# zf1.net
KiCad netlist of a schematic drawn in EAGLE
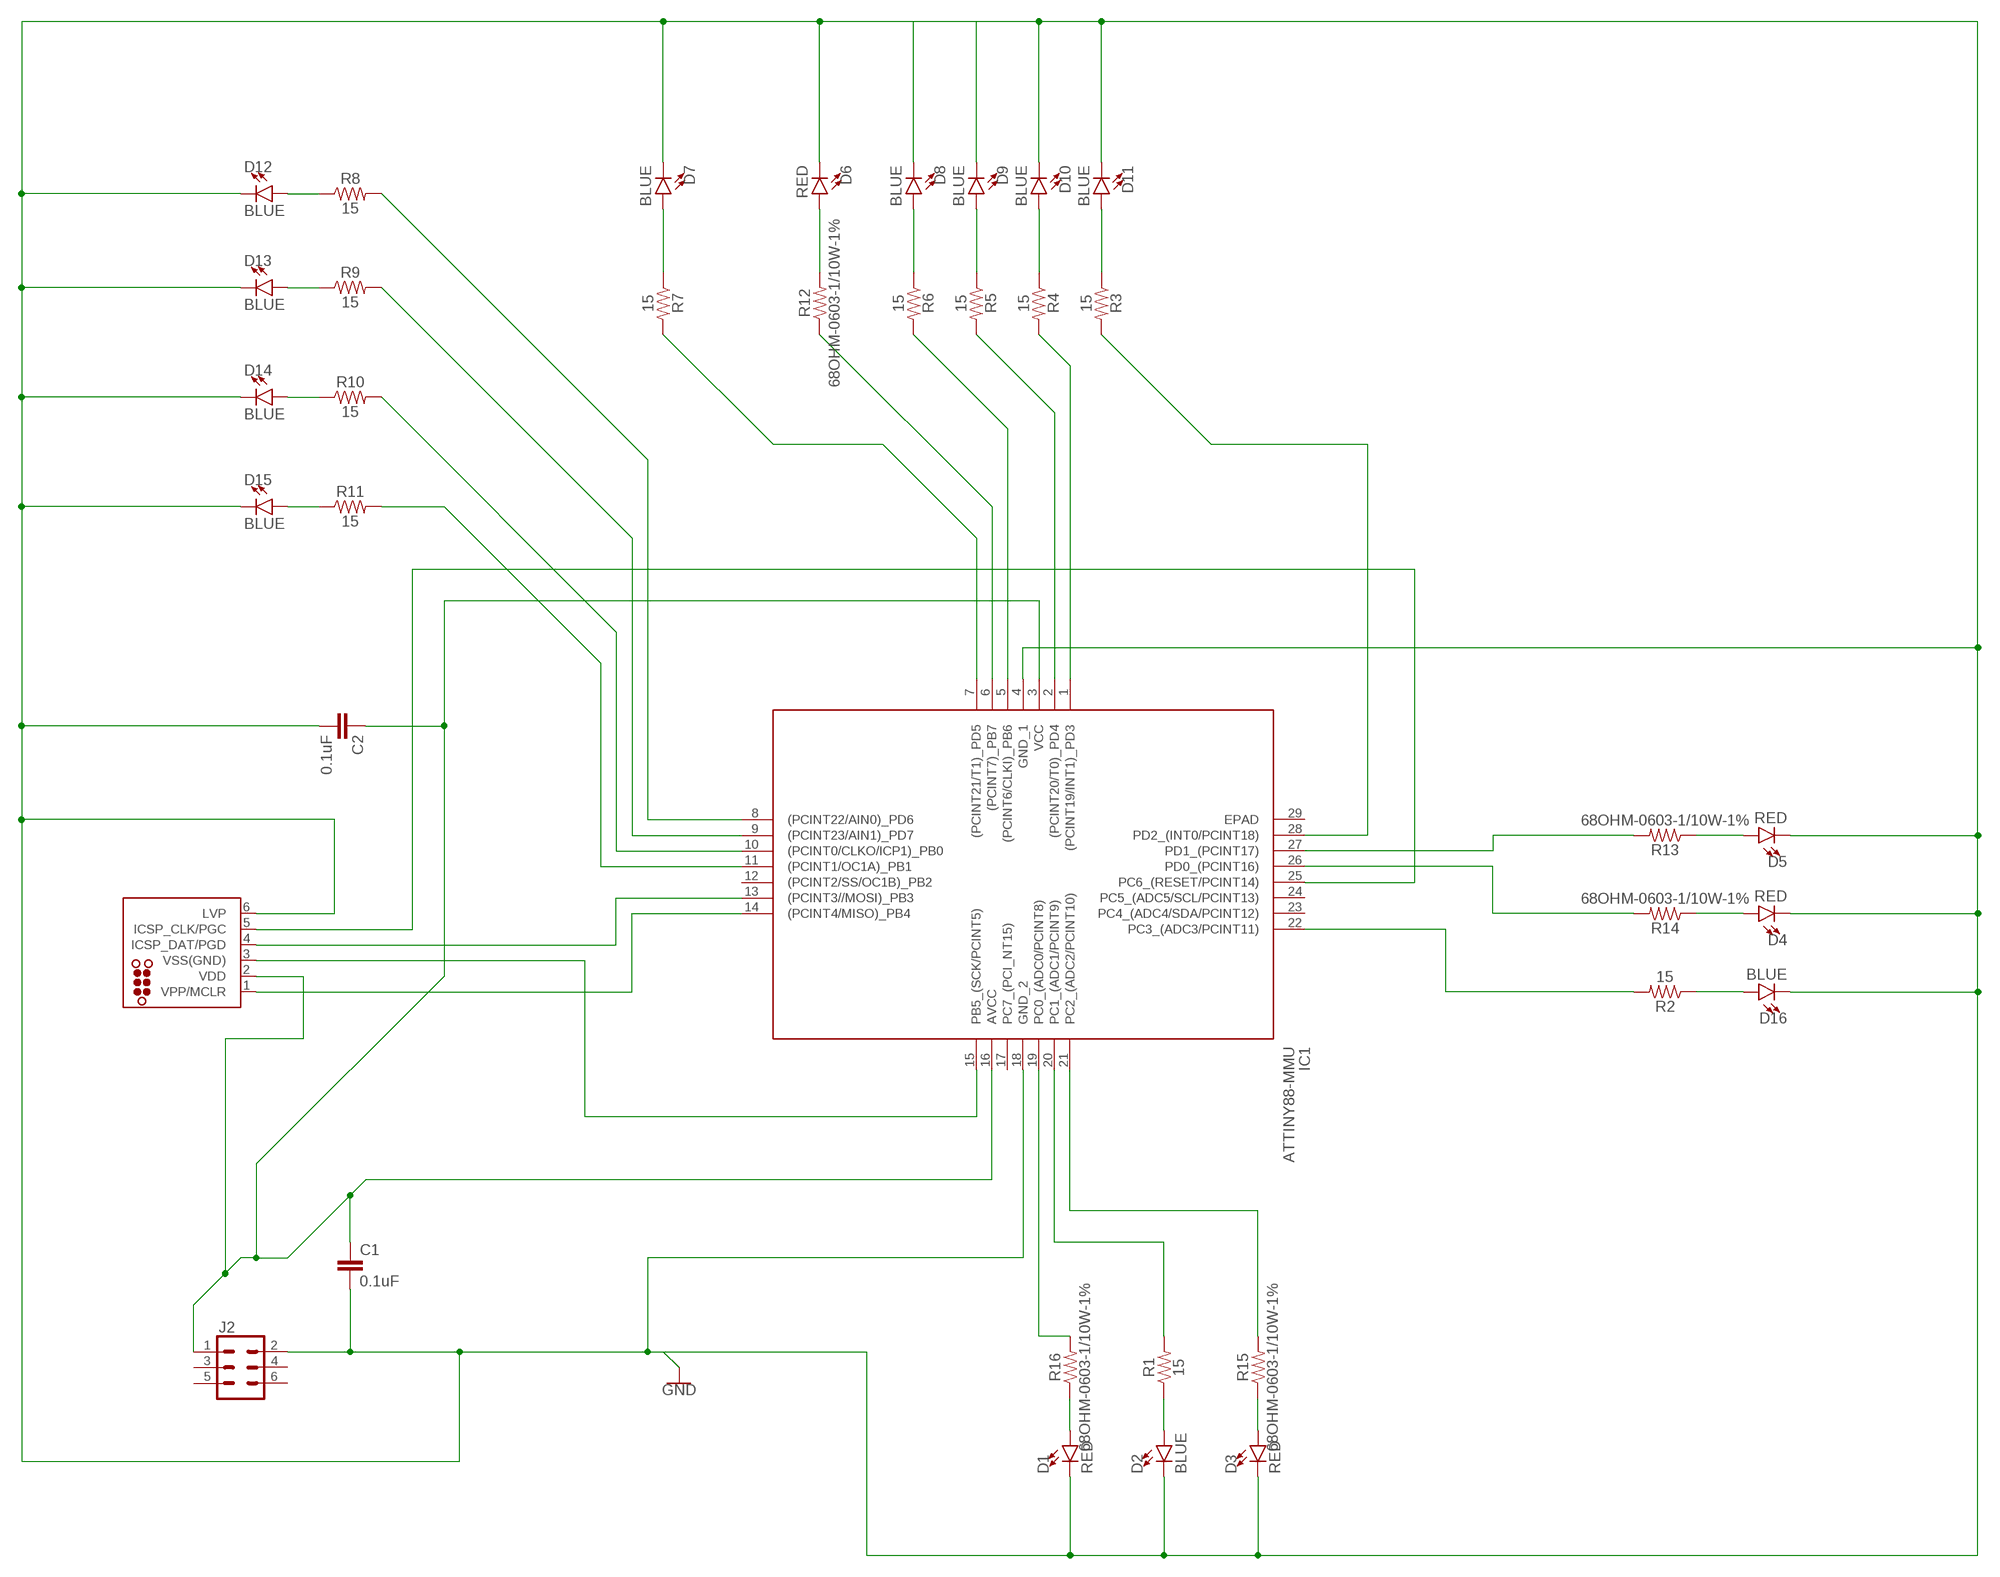
[diagram p0: schematic, sheet 1]

(export (version "E")
  (design (tool "Eeschema 10.0.6"))
  (components
    (comp (ref "C1")
      (value "0.1uF")
      (footprint "eagle-import:0603")
      (libsource (lib "eagle-import") (part "0.1UF-0603-25V-(+80/-20%)"))
    )
    (comp (ref "C2")
      (value "0.1uF")
      (footprint "eagle-import:0603")
      (libsource (lib "eagle-import") (part "0.1UF-0603-25V-(+80/-20%)"))
    )
    (comp (ref "D1")
      (value "RED")
      (footprint "eagle-import:LED-0603")
      (libsource (lib "eagle-import") (part "LED-RED0603"))
    )
    (comp (ref "D2")
      (value "BLUE")
      (footprint "eagle-import:LED-0603")
      (libsource (lib "eagle-import") (part "LED-BLUE0603"))
    )
    (comp (ref "D3")
      (value "RED")
      (footprint "eagle-import:LED-0603")
      (libsource (lib "eagle-import") (part "LED-RED0603"))
    )
    (comp (ref "D4")
      (value "RED")
      (footprint "eagle-import:LED-0603")
      (libsource (lib "eagle-import") (part "LED-RED0603"))
    )
    (comp (ref "D5")
      (value "RED")
      (footprint "eagle-import:LED-0603")
      (libsource (lib "eagle-import") (part "LED-RED0603"))
    )
    (comp (ref "D6")
      (value "RED")
      (footprint "eagle-import:LED-0603")
      (libsource (lib "eagle-import") (part "LED-RED0603"))
    )
    (comp (ref "D7")
      (value "BLUE")
      (footprint "eagle-import:LED-0603")
      (libsource (lib "eagle-import") (part "LED-BLUE0603"))
    )
    (comp (ref "D8")
      (value "BLUE")
      (footprint "eagle-import:LED-0603")
      (libsource (lib "eagle-import") (part "LED-BLUE0603"))
    )
    (comp (ref "D9")
      (value "BLUE")
      (footprint "eagle-import:LED-0603")
      (libsource (lib "eagle-import") (part "LED-BLUE0603"))
    )
    (comp (ref "D10")
      (value "BLUE")
      (footprint "eagle-import:LED-0603")
      (libsource (lib "eagle-import") (part "LED-BLUE0603"))
    )
    (comp (ref "D11")
      (value "BLUE")
      (footprint "eagle-import:LED-0603")
      (libsource (lib "eagle-import") (part "LED-BLUE0603"))
    )
    (comp (ref "D12")
      (value "BLUE")
      (footprint "eagle-import:LED-0603")
      (libsource (lib "eagle-import") (part "LED-BLUE0603"))
    )
    (comp (ref "D13")
      (value "BLUE")
      (footprint "eagle-import:LED-0603")
      (libsource (lib "eagle-import") (part "LED-BLUE0603"))
    )
    (comp (ref "D14")
      (value "BLUE")
      (footprint "eagle-import:LED-0603")
      (libsource (lib "eagle-import") (part "LED-BLUE0603"))
    )
    (comp (ref "D15")
      (value "BLUE")
      (footprint "eagle-import:LED-0603")
      (libsource (lib "eagle-import") (part "LED-BLUE0603"))
    )
    (comp (ref "D16")
      (value "BLUE")
      (footprint "eagle-import:LED-0603")
      (libsource (lib "eagle-import") (part "LED-BLUE0603"))
    )
    (comp (ref "IC1")
      (value "ATTINY88-MMU")
      (footprint "eagle-import:QFN45P400X400X100-29N")
      (fields (field (name "MOUSER_PART_NUMBER") "556-ATTINY88-MMU"))
      (libsource (lib "eagle-import") (part "ATTINY88-MMU"))
    )
    (comp (ref "J1")
      (value "TC2030-MCP-NL")
      (footprint "eagle-import:TC2030-MCP-NL")
      (libsource (lib "eagle-import") (part "TC2030-MCP-NL"))
    )
    (comp (ref "J2")
      (value "CONN_03X2SHROUD")
      (footprint "eagle-import:2X3-SHROUDED")
      (libsource (lib "eagle-import") (part "CONN_03X2SHROUD"))
    )
    (comp (ref "R1")
      (value "15")
      (footprint "eagle-import:0603")
      (libsource (lib "eagle-import") (part "15OHM-0603-1/10W-1%"))
    )
    (comp (ref "R2")
      (value "15")
      (footprint "eagle-import:0603")
      (libsource (lib "eagle-import") (part "15OHM-0603-1/10W-1%"))
    )
    (comp (ref "R3")
      (value "15")
      (footprint "eagle-import:0603")
      (libsource (lib "eagle-import") (part "15OHM-0603-1/10W-1%"))
    )
    (comp (ref "R4")
      (value "15")
      (footprint "eagle-import:0603")
      (libsource (lib "eagle-import") (part "15OHM-0603-1/10W-1%"))
    )
    (comp (ref "R5")
      (value "15")
      (footprint "eagle-import:0603")
      (libsource (lib "eagle-import") (part "15OHM-0603-1/10W-1%"))
    )
    (comp (ref "R6")
      (value "15")
      (footprint "eagle-import:0603")
      (libsource (lib "eagle-import") (part "15OHM-0603-1/10W-1%"))
    )
    (comp (ref "R7")
      (value "15")
      (footprint "eagle-import:0603")
      (libsource (lib "eagle-import") (part "15OHM-0603-1/10W-1%"))
    )
    (comp (ref "R8")
      (value "15")
      (footprint "eagle-import:0603")
      (libsource (lib "eagle-import") (part "15OHM-0603-1/10W-1%"))
    )
    (comp (ref "R9")
      (value "15")
      (footprint "eagle-import:0603")
      (libsource (lib "eagle-import") (part "15OHM-0603-1/10W-1%"))
    )
    (comp (ref "R10")
      (value "15")
      (footprint "eagle-import:0603")
      (libsource (lib "eagle-import") (part "15OHM-0603-1/10W-1%"))
    )
    (comp (ref "R11")
      (value "15")
      (footprint "eagle-import:0603")
      (libsource (lib "eagle-import") (part "15OHM-0603-1/10W-1%"))
    )
    (comp (ref "R12")
      (value "68OHM-0603-1/10W-1%")
      (footprint "eagle-import:0603")
      (libsource (lib "eagle-import") (part "68OHM-0603-1/10W-1%"))
    )
    (comp (ref "R13")
      (value "68OHM-0603-1/10W-1%")
      (footprint "eagle-import:0603")
      (libsource (lib "eagle-import") (part "68OHM-0603-1/10W-1%"))
    )
    (comp (ref "R14")
      (value "68OHM-0603-1/10W-1%")
      (footprint "eagle-import:0603")
      (libsource (lib "eagle-import") (part "68OHM-0603-1/10W-1%"))
    )
    (comp (ref "R15")
      (value "68OHM-0603-1/10W-1%")
      (footprint "eagle-import:0603")
      (libsource (lib "eagle-import") (part "68OHM-0603-1/10W-1%"))
    )
    (comp (ref "R16")
      (value "68OHM-0603-1/10W-1%")
      (footprint "eagle-import:0603")
      (libsource (lib "eagle-import") (part "68OHM-0603-1/10W-1%"))
    )
  )
  (nets
    (net (code "1") (name "GND") (class "Default")
      (node (ref "C1") (pin "2") (pinfunction "2_2") (pintype "passive"))
      (node (ref "C2") (pin "2") (pinfunction "2_2") (pintype "passive"))
      (node (ref "D1") (pin "C") (pinfunction "C_C") (pintype "passive"))
      (node (ref "D10") (pin "C") (pinfunction "C_C") (pintype "passive"))
      (node (ref "D11") (pin "C") (pinfunction "C_C") (pintype "passive"))
      (node (ref "D12") (pin "C") (pinfunction "C_C") (pintype "passive"))
      (node (ref "D13") (pin "C") (pinfunction "C_C") (pintype "passive"))
      (node (ref "D14") (pin "C") (pinfunction "C_C") (pintype "passive"))
      (node (ref "D15") (pin "C") (pinfunction "C_C") (pintype "passive"))
      (node (ref "D16") (pin "C") (pinfunction "C_C") (pintype "passive"))
      (node (ref "D2") (pin "C") (pinfunction "C_C") (pintype "passive"))
      (node (ref "D3") (pin "C") (pinfunction "C_C") (pintype "passive"))
      (node (ref "D4") (pin "C") (pinfunction "C_C") (pintype "passive"))
      (node (ref "D5") (pin "C") (pinfunction "C_C") (pintype "passive"))
      (node (ref "D6") (pin "C") (pinfunction "C_C") (pintype "passive"))
      (node (ref "D7") (pin "C") (pinfunction "C_C") (pintype "passive"))
      (node (ref "D8") (pin "C") (pinfunction "C_C") (pintype "passive"))
      (node (ref "D9") (pin "C") (pinfunction "C_C") (pintype "passive"))
      (node (ref "IC1") (pin "18") (pinfunction "GND_2_18") (pintype "bidirectional"))
      (node (ref "IC1") (pin "4") (pinfunction "GND_1_4") (pintype "bidirectional"))
      (node (ref "J1") (pin "6") (pinfunction "LVP_6") (pintype "bidirectional"))
      (node (ref "J2") (pin "2") (pinfunction "2_2") (pintype "bidirectional"))
    )
    (net (code "2") (name "Net-(D1-PadA)") (class "Default")
      (node (ref "D1") (pin "A") (pinfunction "A_A") (pintype "passive"))
      (node (ref "R16") (pin "1") (pinfunction "1_1") (pintype "passive"))
    )
    (net (code "3") (name "Net-(D2-PadA)") (class "Default")
      (node (ref "D2") (pin "A") (pinfunction "A_A") (pintype "passive"))
      (node (ref "R1") (pin "1") (pinfunction "1_1") (pintype "passive"))
    )
    (net (code "4") (name "Net-(D3-PadA)") (class "Default")
      (node (ref "D3") (pin "A") (pinfunction "A_A") (pintype "passive"))
      (node (ref "R15") (pin "1") (pinfunction "1_1") (pintype "passive"))
    )
    (net (code "5") (name "Net-(D4-PadA)") (class "Default")
      (node (ref "D4") (pin "A") (pinfunction "A_A") (pintype "passive"))
      (node (ref "R14") (pin "1") (pinfunction "1_1") (pintype "passive"))
    )
    (net (code "6") (name "Net-(D5-PadA)") (class "Default")
      (node (ref "D5") (pin "A") (pinfunction "A_A") (pintype "passive"))
      (node (ref "R13") (pin "1") (pinfunction "1_1") (pintype "passive"))
    )
    (net (code "7") (name "Net-(D6-PadA)") (class "Default")
      (node (ref "D6") (pin "A") (pinfunction "A_A") (pintype "passive"))
      (node (ref "R12") (pin "2") (pinfunction "2_2") (pintype "passive"))
    )
    (net (code "8") (name "Net-(D7-PadA)") (class "Default")
      (node (ref "D7") (pin "A") (pinfunction "A_A") (pintype "passive"))
      (node (ref "R7") (pin "1") (pinfunction "1_1") (pintype "passive"))
    )
    (net (code "9") (name "Net-(D8-PadA)") (class "Default")
      (node (ref "D8") (pin "A") (pinfunction "A_A") (pintype "passive"))
      (node (ref "R6") (pin "1") (pinfunction "1_1") (pintype "passive"))
    )
    (net (code "10") (name "Net-(D9-PadA)") (class "Default")
      (node (ref "D9") (pin "A") (pinfunction "A_A") (pintype "passive"))
      (node (ref "R5") (pin "1") (pinfunction "1_1") (pintype "passive"))
    )
    (net (code "11") (name "Net-(D10-PadA)") (class "Default")
      (node (ref "D10") (pin "A") (pinfunction "A_A") (pintype "passive"))
      (node (ref "R4") (pin "1") (pinfunction "1_1") (pintype "passive"))
    )
    (net (code "12") (name "Net-(D11-PadA)") (class "Default")
      (node (ref "D11") (pin "A") (pinfunction "A_A") (pintype "passive"))
      (node (ref "R3") (pin "1") (pinfunction "1_1") (pintype "passive"))
    )
    (net (code "13") (name "Net-(D12-PadA)") (class "Default")
      (node (ref "D12") (pin "A") (pinfunction "A_A") (pintype "passive"))
      (node (ref "R8") (pin "1") (pinfunction "1_1") (pintype "passive"))
    )
    (net (code "14") (name "Net-(D13-PadA)") (class "Default")
      (node (ref "D13") (pin "A") (pinfunction "A_A") (pintype "passive"))
      (node (ref "R9") (pin "1") (pinfunction "1_1") (pintype "passive"))
    )
    (net (code "15") (name "Net-(D14-PadA)") (class "Default")
      (node (ref "D14") (pin "A") (pinfunction "A_A") (pintype "passive"))
      (node (ref "R10") (pin "1") (pinfunction "1_1") (pintype "passive"))
    )
    (net (code "16") (name "Net-(D15-PadA)") (class "Default")
      (node (ref "D15") (pin "A") (pinfunction "A_A") (pintype "passive"))
      (node (ref "R11") (pin "1") (pinfunction "1_1") (pintype "passive"))
    )
    (net (code "17") (name "Net-(D16-PadA)") (class "Default")
      (node (ref "D16") (pin "A") (pinfunction "A_A") (pintype "passive"))
      (node (ref "R2") (pin "1") (pinfunction "1_1") (pintype "passive"))
    )
    (net (code "18") (name "Net-(IC1-(PCINT0{slash}CLKO{slash}ICP1)_PB0)") (class "Default")
      (node (ref "IC1") (pin "10") (pinfunction "(PCINT0/CLKO/ICP1)_PB0_10") (pintype "bidirectional"))
      (node (ref "R10") (pin "2") (pinfunction "2_2") (pintype "passive"))
    )
    (net (code "19") (name "Net-(IC1-(PCINT1{slash}OC1A)_PB1)") (class "Default")
      (node (ref "IC1") (pin "11") (pinfunction "(PCINT1/OC1A)_PB1_11") (pintype "bidirectional"))
      (node (ref "R11") (pin "2") (pinfunction "2_2") (pintype "passive"))
    )
    (net (code "20") (name "Net-(IC1-(PCINT3{slash}{slash}MOSI)_PB3)") (class "Default")
      (node (ref "IC1") (pin "13") (pinfunction "(PCINT3//MOSI)_PB3_13") (pintype "bidirectional"))
      (node (ref "J1") (pin "4") (pinfunction "ICSP_DAT/PGD_4") (pintype "bidirectional"))
    )
    (net (code "21") (name "Net-(IC1-(PCINT4{slash}MISO)_PB4)") (class "Default")
      (node (ref "IC1") (pin "14") (pinfunction "(PCINT4/MISO)_PB4_14") (pintype "bidirectional"))
      (node (ref "J1") (pin "1") (pinfunction "VPP/MCLR_1") (pintype "passive"))
    )
    (net (code "22") (name "Net-(IC1-(PCINT6{slash}CLKI)_PB6)") (class "Default")
      (node (ref "IC1") (pin "5") (pinfunction "(PCINT6/CLKI)_PB6_5") (pintype "bidirectional"))
      (node (ref "R6") (pin "2") (pinfunction "2_2") (pintype "passive"))
    )
    (net (code "23") (name "Net-(IC1-(PCINT7)_PB7)") (class "Default")
      (node (ref "IC1") (pin "6") (pinfunction "(PCINT7)_PB7_6") (pintype "bidirectional"))
      (node (ref "R12") (pin "1") (pinfunction "1_1") (pintype "passive"))
    )
    (net (code "24") (name "Net-(IC1-(PCINT19{slash}INT1)_PD3)") (class "Default")
      (node (ref "IC1") (pin "1") (pinfunction "(PCINT19/INT1)_PD3_1") (pintype "bidirectional"))
      (node (ref "R4") (pin "2") (pinfunction "2_2") (pintype "passive"))
    )
    (net (code "25") (name "Net-(IC1-(PCINT20{slash}T0)_PD4)") (class "Default")
      (node (ref "IC1") (pin "2") (pinfunction "(PCINT20/T0)_PD4_2") (pintype "bidirectional"))
      (node (ref "R5") (pin "2") (pinfunction "2_2") (pintype "passive"))
    )
    (net (code "26") (name "Net-(IC1-(PCINT21{slash}T1)_PD5)") (class "Default")
      (node (ref "IC1") (pin "7") (pinfunction "(PCINT21/T1)_PD5_7") (pintype "bidirectional"))
      (node (ref "R7") (pin "2") (pinfunction "2_2") (pintype "passive"))
    )
    (net (code "27") (name "Net-(IC1-(PCINT22{slash}AIN0)_PD6)") (class "Default")
      (node (ref "IC1") (pin "8") (pinfunction "(PCINT22/AIN0)_PD6_8") (pintype "bidirectional"))
      (node (ref "R8") (pin "2") (pinfunction "2_2") (pintype "passive"))
    )
    (net (code "28") (name "Net-(IC1-(PCINT23{slash}AIN1)_PD7)") (class "Default")
      (node (ref "IC1") (pin "9") (pinfunction "(PCINT23/AIN1)_PD7_9") (pintype "bidirectional"))
      (node (ref "R9") (pin "2") (pinfunction "2_2") (pintype "passive"))
    )
    (net (code "29") (name "Net-(IC1-AVCC)") (class "Default")
      (node (ref "C1") (pin "1") (pinfunction "1_1") (pintype "passive"))
      (node (ref "C2") (pin "1") (pinfunction "1_1") (pintype "passive"))
      (node (ref "IC1") (pin "16") (pinfunction "AVCC_16") (pintype "bidirectional"))
      (node (ref "IC1") (pin "3") (pinfunction "VCC_3") (pintype "bidirectional"))
      (node (ref "J1") (pin "2") (pinfunction "VDD_2") (pintype "power_in"))
      (node (ref "J2") (pin "1") (pinfunction "1_1") (pintype "bidirectional"))
    )
    (net (code "30") (name "Net-(IC1-PB5_(SCK{slash}PCINT5))") (class "Default")
      (node (ref "IC1") (pin "15") (pinfunction "PB5_(SCK/PCINT5)_15") (pintype "bidirectional"))
      (node (ref "J1") (pin "3") (pinfunction "VSS(GND)_3") (pintype "power_in"))
    )
    (net (code "31") (name "Net-(IC1-PC0_(ADC0{slash}PCINT8))") (class "Default")
      (node (ref "IC1") (pin "19") (pinfunction "PC0_(ADC0/PCINT8)_19") (pintype "bidirectional"))
      (node (ref "R16") (pin "2") (pinfunction "2_2") (pintype "passive"))
    )
    (net (code "32") (name "Net-(IC1-PC1_(ADC1{slash}PCINT9))") (class "Default")
      (node (ref "IC1") (pin "20") (pinfunction "PC1_(ADC1/PCINT9)_20") (pintype "bidirectional"))
      (node (ref "R1") (pin "2") (pinfunction "2_2") (pintype "passive"))
    )
    (net (code "33") (name "Net-(IC1-PC2_(ADC2{slash}PCINT10))") (class "Default")
      (node (ref "IC1") (pin "21") (pinfunction "PC2_(ADC2/PCINT10)_21") (pintype "bidirectional"))
      (node (ref "R15") (pin "2") (pinfunction "2_2") (pintype "passive"))
    )
    (net (code "34") (name "Net-(IC1-PC3_(ADC3{slash}PCINT11))") (class "Default")
      (node (ref "IC1") (pin "22") (pinfunction "PC3_(ADC3/PCINT11)_22") (pintype "bidirectional"))
      (node (ref "R2") (pin "2") (pinfunction "2_2") (pintype "passive"))
    )
    (net (code "35") (name "Net-(IC1-PC6_(RESET{slash}PCINT14))") (class "Default")
      (node (ref "IC1") (pin "25") (pinfunction "PC6_(RESET/PCINT14)_25") (pintype "bidirectional"))
      (node (ref "J1") (pin "5") (pinfunction "ICSP_CLK/PGC_5") (pintype "output"))
    )
    (net (code "36") (name "Net-(IC1-PD0_(PCINT16))") (class "Default")
      (node (ref "IC1") (pin "26") (pinfunction "PD0_(PCINT16)_26") (pintype "bidirectional"))
      (node (ref "R14") (pin "2") (pinfunction "2_2") (pintype "passive"))
    )
    (net (code "37") (name "Net-(IC1-PD1_(PCINT17))") (class "Default")
      (node (ref "IC1") (pin "27") (pinfunction "PD1_(PCINT17)_27") (pintype "bidirectional"))
      (node (ref "R13") (pin "2") (pinfunction "2_2") (pintype "passive"))
    )
    (net (code "38") (name "Net-(IC1-PD2_(INT0{slash}PCINT18))") (class "Default")
      (node (ref "IC1") (pin "28") (pinfunction "PD2_(INT0/PCINT18)_28") (pintype "bidirectional"))
      (node (ref "R3") (pin "2") (pinfunction "2_2") (pintype "passive"))
    )
    (net (code "39") (name "unconnected-(IC1-(PCINT2{slash}SS{slash}OC1B)_PB2-Pad12)") (class "Default")
      (node (ref "IC1") (pin "12") (pinfunction "(PCINT2/SS/OC1B)_PB2_12") (pintype "bidirectional"))
    )
    (net (code "40") (name "unconnected-(IC1-EPAD-Pad29)") (class "Default")
      (node (ref "IC1") (pin "29") (pinfunction "EPAD_29") (pintype "bidirectional"))
    )
    (net (code "41") (name "unconnected-(IC1-PC4_(ADC4{slash}SDA{slash}PCINT12)-Pad23)") (class "Default")
      (node (ref "IC1") (pin "23") (pinfunction "PC4_(ADC4/SDA/PCINT12)_23") (pintype "bidirectional"))
    )
    (net (code "42") (name "unconnected-(IC1-PC5_(ADC5{slash}SCL{slash}PCINT13)-Pad24)") (class "Default")
      (node (ref "IC1") (pin "24") (pinfunction "PC5_(ADC5/SCL/PCINT13)_24") (pintype "bidirectional"))
    )
    (net (code "43") (name "unconnected-(IC1-PC7_(PCI_NT15)-Pad17)") (class "Default")
      (node (ref "IC1") (pin "17") (pinfunction "PC7_(PCI_NT15)_17") (pintype "bidirectional"))
    )
    (net (code "44") (name "unconnected-(J2-Pad3)") (class "Default")
      (node (ref "J2") (pin "3") (pinfunction "3_3") (pintype "bidirectional"))
    )
    (net (code "45") (name "unconnected-(J2-Pad4)") (class "Default")
      (node (ref "J2") (pin "4") (pinfunction "4_4") (pintype "bidirectional"))
    )
    (net (code "46") (name "unconnected-(J2-Pad5)") (class "Default")
      (node (ref "J2") (pin "5") (pinfunction "5_5") (pintype "bidirectional"))
    )
    (net (code "47") (name "unconnected-(J2-Pad6)") (class "Default")
      (node (ref "J2") (pin "6") (pinfunction "6_6") (pintype "bidirectional"))
    )
  )
)
